# Liftmaster78LM.net
KiCad netlist of a schematic drawn in EAGLE
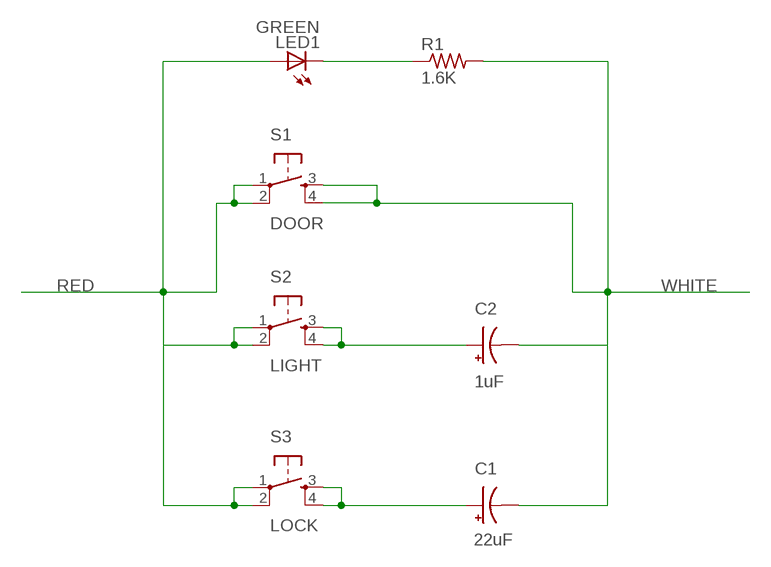
[diagram p0: schematic, sheet 1]

(export (version "E")
  (design (tool "Eeschema 10.0.6"))
  (components
    (comp (ref "C1")
      (value "22uF")
      (footprint "eagle-import:E2-5")
      (libsource (lib "eagle-import") (part "CPOL-USE2-5"))
    )
    (comp (ref "C2")
      (value "1uF")
      (footprint "eagle-import:E2-5")
      (libsource (lib "eagle-import") (part "CPOL-USE2-5"))
    )
    (comp (ref "LED1")
      (value "GREEN")
      (footprint "eagle-import:LED3MM")
      (fields (field (name "MF") "VISHAY SEMICONDUCTOR"))
      (libsource (lib "eagle-import") (part "TLLG4400"))
    )
    (comp (ref "R1")
      (value "1.6K")
      (footprint "eagle-import:0207_10")
      (libsource (lib "eagle-import") (part "R-US_0207/10"))
    )
    (comp (ref "S1")
      (value "DOOR")
      (footprint "eagle-import:TACTILE_SWITCH_SMD")
      (libsource (lib "eagle-import") (part "TAC_SWITCHSMD"))
    )
    (comp (ref "S2")
      (value "LIGHT")
      (footprint "eagle-import:TACTILE_SWITCH_SMD")
      (libsource (lib "eagle-import") (part "TAC_SWITCHSMD"))
    )
    (comp (ref "S3")
      (value "LOCK")
      (footprint "eagle-import:TACTILE_SWITCH_SMD")
      (libsource (lib "eagle-import") (part "TAC_SWITCHSMD"))
    )
  )
  (nets
    (net (code "1") (name "/RED") (class "Default")
      (node (ref "LED1") (pin "A") (pinfunction "A_A") (pintype "passive"))
      (node (ref "S1") (pin "1") (pinfunction "1_1") (pintype "passive"))
      (node (ref "S1") (pin "2") (pinfunction "2_2") (pintype "passive"))
      (node (ref "S2") (pin "1") (pinfunction "1_1") (pintype "passive"))
      (node (ref "S2") (pin "2") (pinfunction "2_2") (pintype "passive"))
      (node (ref "S3") (pin "1") (pinfunction "1_1") (pintype "passive"))
      (node (ref "S3") (pin "2") (pinfunction "2_2") (pintype "passive"))
    )
    (net (code "2") (name "/WHITE") (class "Default")
      (node (ref "C1") (pin "-") (pinfunction "-_-") (pintype "passive"))
      (node (ref "C2") (pin "-") (pinfunction "-_-") (pintype "passive"))
      (node (ref "R1") (pin "2") (pinfunction "2_2") (pintype "passive"))
      (node (ref "S1") (pin "3") (pinfunction "3_3") (pintype "passive"))
      (node (ref "S1") (pin "4") (pinfunction "4_4") (pintype "passive"))
    )
    (net (code "3") (name "Net-(C1-Pad+)") (class "Default")
      (node (ref "C1") (pin "+") (pinfunction "+_+") (pintype "passive"))
      (node (ref "S3") (pin "3") (pinfunction "3_3") (pintype "passive"))
      (node (ref "S3") (pin "4") (pinfunction "4_4") (pintype "passive"))
    )
    (net (code "4") (name "Net-(C2-Pad+)") (class "Default")
      (node (ref "C2") (pin "+") (pinfunction "+_+") (pintype "passive"))
      (node (ref "S2") (pin "3") (pinfunction "3_3") (pintype "passive"))
      (node (ref "S2") (pin "4") (pinfunction "4_4") (pintype "passive"))
    )
    (net (code "5") (name "Net-(LED1-C)") (class "Default")
      (node (ref "LED1") (pin "K") (pinfunction "C_K") (pintype "passive"))
      (node (ref "R1") (pin "1") (pinfunction "1_1") (pintype "passive"))
    )
  )
)
